# PDS_JSTConnections.net
KiCad netlist of a schematic drawn in Altium Designer
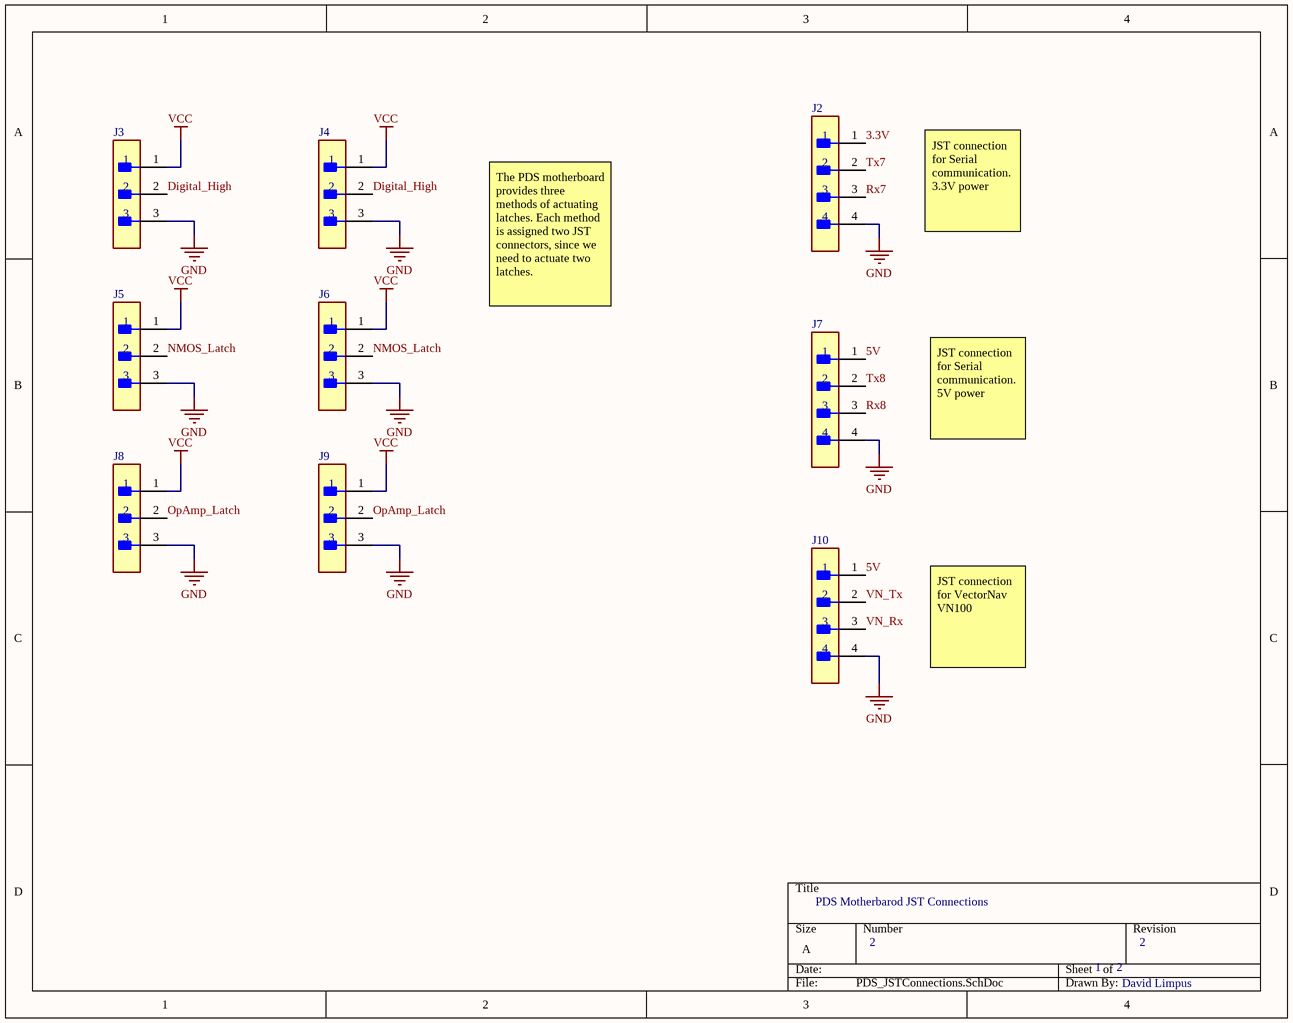
[diagram p0: PDS_JSTConnections.SchDoc]

(export (version "E")
  (design (tool "Eeschema 10.0.6"))
  (components
    (comp (ref "J2")
      (value "B04B-XASK-1-A(LF)(SN)")
      (footprint "FP-B04B-XASK-1-A_LF_SN-MFG")
      (description "CONN HEADER VERT POS 2.5MM")
      (libsource (lib "Altium Content Vault") (part "299a8cea1bdcbc3624fe62c390fa72c"))
    )
    (comp (ref "J3")
      (value "B03B-XASK-1-A(LF)(SN)")
      (footprint "FP-B03B-XASK-1-A_LF_SN-MFG")
      (description "CONN HEADER VERT 3POS 2.5MM")
      (libsource (lib "Altium Content Vault") (part "0d3f023dd272f625e17a2be33dea85f"))
    )
    (comp (ref "J4")
      (value "B03B-XASK-1-A(LF)(SN)")
      (footprint "FP-B03B-XASK-1-A_LF_SN-MFG")
      (description "CONN HEADER VERT 3POS 2.5MM")
      (libsource (lib "Altium Content Vault") (part "0d3f023dd272f625e17a2be33dea85f"))
    )
    (comp (ref "J5")
      (value "B03B-XASK-1-A(LF)(SN)")
      (footprint "FP-B03B-XASK-1-A_LF_SN-MFG")
      (description "CONN HEADER VERT 3POS 2.5MM")
      (libsource (lib "Altium Content Vault") (part "0d3f023dd272f625e17a2be33dea85f"))
    )
    (comp (ref "J6")
      (value "B03B-XASK-1-A(LF)(SN)")
      (footprint "FP-B03B-XASK-1-A_LF_SN-MFG")
      (description "CONN HEADER VERT 3POS 2.5MM")
      (libsource (lib "Altium Content Vault") (part "0d3f023dd272f625e17a2be33dea85f"))
    )
    (comp (ref "J7")
      (value "B04B-XASK-1-A(LF)(SN)")
      (footprint "FP-B04B-XASK-1-A_LF_SN-MFG")
      (description "CONN HEADER VERT POS 2.5MM")
      (libsource (lib "Altium Content Vault") (part "299a8cea1bdcbc3624fe62c390fa72c"))
    )
    (comp (ref "J8")
      (value "B03B-XASK-1-A(LF)(SN)")
      (footprint "FP-B03B-XASK-1-A_LF_SN-MFG")
      (description "CONN HEADER VERT 3POS 2.5MM")
      (libsource (lib "Altium Content Vault") (part "0d3f023dd272f625e17a2be33dea85f"))
    )
    (comp (ref "J9")
      (value "B03B-XASK-1-A(LF)(SN)")
      (footprint "FP-B03B-XASK-1-A_LF_SN-MFG")
      (description "CONN HEADER VERT 3POS 2.5MM")
      (libsource (lib "Altium Content Vault") (part "0d3f023dd272f625e17a2be33dea85f"))
    )
    (comp (ref "J10")
      (value "B04B-XASK-1-A(LF)(SN)")
      (footprint "FP-B04B-XASK-1-A_LF_SN-MFG")
      (description "CONN HEADER VERT POS 2.5MM")
      (libsource (lib "Altium Content Vault") (part "299a8cea1bdcbc3624fe62c390fa72c"))
    )
  )
  (nets
    (net (code "1") (name "/3.3V") (class "Default")
      (node (ref "J2") (pin "1") (pinfunction "1_1") (pintype "passive"))
    )
    (net (code "2") (name "/5V") (class "Default")
      (node (ref "J10") (pin "1") (pinfunction "1_1") (pintype "passive"))
      (node (ref "J7") (pin "1") (pinfunction "1_1") (pintype "passive"))
    )
    (net (code "3") (name "/Digital_High") (class "Default")
      (node (ref "J3") (pin "2") (pinfunction "2_2") (pintype "passive"))
      (node (ref "J4") (pin "2") (pinfunction "2_2") (pintype "passive"))
    )
    (net (code "4") (name "/NMOS_Latch") (class "Default")
      (node (ref "J5") (pin "2") (pinfunction "2_2") (pintype "passive"))
      (node (ref "J6") (pin "2") (pinfunction "2_2") (pintype "passive"))
    )
    (net (code "5") (name "/OpAmp_Latch") (class "Default")
      (node (ref "J8") (pin "2") (pinfunction "2_2") (pintype "passive"))
      (node (ref "J9") (pin "2") (pinfunction "2_2") (pintype "passive"))
    )
    (net (code "6") (name "/Rx7") (class "Default")
      (node (ref "J2") (pin "3") (pinfunction "3_3") (pintype "passive"))
    )
    (net (code "7") (name "/Rx8") (class "Default")
      (node (ref "J7") (pin "3") (pinfunction "3_3") (pintype "passive"))
    )
    (net (code "8") (name "/Tx7") (class "Default")
      (node (ref "J2") (pin "2") (pinfunction "2_2") (pintype "passive"))
    )
    (net (code "9") (name "/Tx8") (class "Default")
      (node (ref "J7") (pin "2") (pinfunction "2_2") (pintype "passive"))
    )
    (net (code "10") (name "/VN_Rx") (class "Default")
      (node (ref "J10") (pin "3") (pinfunction "3_3") (pintype "passive"))
    )
    (net (code "11") (name "/VN_Tx") (class "Default")
      (node (ref "J10") (pin "2") (pinfunction "2_2") (pintype "passive"))
    )
    (net (code "12") (name "GND") (class "Default")
      (node (ref "J10") (pin "4") (pinfunction "4_4") (pintype "passive"))
      (node (ref "J2") (pin "4") (pinfunction "4_4") (pintype "passive"))
      (node (ref "J3") (pin "3") (pinfunction "3_3") (pintype "passive"))
      (node (ref "J4") (pin "3") (pinfunction "3_3") (pintype "passive"))
      (node (ref "J5") (pin "3") (pinfunction "3_3") (pintype "passive"))
      (node (ref "J6") (pin "3") (pinfunction "3_3") (pintype "passive"))
      (node (ref "J7") (pin "4") (pinfunction "4_4") (pintype "passive"))
      (node (ref "J8") (pin "3") (pinfunction "3_3") (pintype "passive"))
      (node (ref "J9") (pin "3") (pinfunction "3_3") (pintype "passive"))
    )
    (net (code "13") (name "VCC") (class "Default")
      (node (ref "J3") (pin "1") (pinfunction "1_1") (pintype "passive"))
      (node (ref "J4") (pin "1") (pinfunction "1_1") (pintype "passive"))
      (node (ref "J5") (pin "1") (pinfunction "1_1") (pintype "passive"))
      (node (ref "J6") (pin "1") (pinfunction "1_1") (pintype "passive"))
      (node (ref "J8") (pin "1") (pinfunction "1_1") (pintype "passive"))
      (node (ref "J9") (pin "1") (pinfunction "1_1") (pintype "passive"))
    )
  )
)
